# audio.net
KiCad netlist of a schematic drawn in Altium Designer
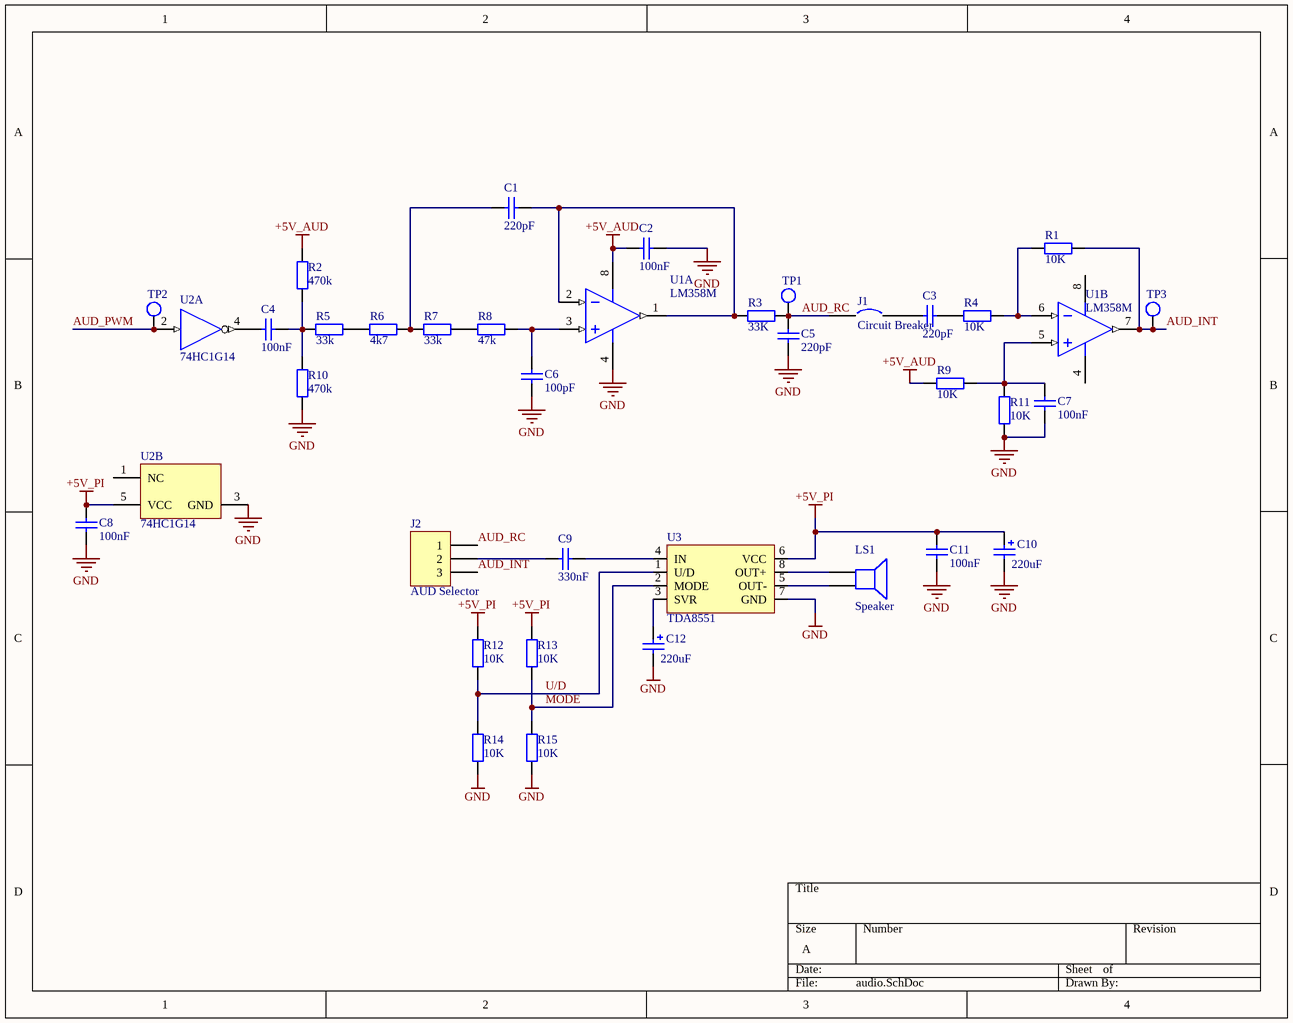
[diagram p0: audio.SchDoc]

(export (version "E")
  (design (tool "Eeschema 10.0.6"))
  (components
    (comp (ref "C1")
      (value "220pF")
      (footprint "6-0805_M")
      (description "Capacitor")
      (fields (field (name "Comment") "Cap") (field (name "PUBLISHER") "Altium Limited"))
      (libsource (lib "Miscellaneous Devices") (part "Cap"))
    )
    (comp (ref "C2")
      (value "100nF")
      (footprint "6-0805_M")
      (description "Capacitor")
      (fields (field (name "Comment") "Cap") (field (name "PUBLISHER") "Altium Limited"))
      (libsource (lib "Miscellaneous Devices") (part "Cap"))
    )
    (comp (ref "C3")
      (value "220pF")
      (footprint "6-0805_M")
      (description "Capacitor")
      (fields (field (name "Comment") "Cap") (field (name "PUBLISHER") "Altium Limited"))
      (libsource (lib "Miscellaneous Devices") (part "Cap"))
    )
    (comp (ref "C4")
      (value "100nF")
      (footprint "6-0805_M")
      (description "Capacitor")
      (fields (field (name "Comment") "Cap") (field (name "PUBLISHER") "Altium Limited"))
      (libsource (lib "Miscellaneous Devices") (part "Cap"))
    )
    (comp (ref "C5")
      (value "220pF")
      (footprint "6-0805_M")
      (description "Capacitor")
      (fields (field (name "Comment") "Cap") (field (name "PUBLISHER") "Altium Limited"))
      (libsource (lib "Miscellaneous Devices") (part "Cap"))
    )
    (comp (ref "C6")
      (value "100pF")
      (footprint "6-0805_M")
      (description "Capacitor")
      (fields (field (name "Comment") "Cap") (field (name "PUBLISHER") "Altium Limited"))
      (libsource (lib "Miscellaneous Devices") (part "Cap"))
    )
    (comp (ref "C7")
      (value "100nF")
      (footprint "6-0805_M")
      (description "Capacitor")
      (fields (field (name "Comment") "Cap") (field (name "PUBLISHER") "Altium Limited"))
      (libsource (lib "Miscellaneous Devices") (part "Cap"))
    )
    (comp (ref "C8")
      (value "100nF")
      (footprint "6-0805_M")
      (description "Capacitor")
      (fields (field (name "Comment") "Cap") (field (name "PUBLISHER") "Altium Limited"))
      (libsource (lib "Miscellaneous Devices") (part "Cap"))
    )
    (comp (ref "C9")
      (value "330nF")
      (footprint "6-0805_M")
      (description "Capacitor")
      (fields (field (name "Comment") "Cap") (field (name "PUBLISHER") "Altium Limited"))
      (libsource (lib "Miscellaneous Devices") (part "Cap"))
    )
    (comp (ref "C10")
      (value "220uF")
      (footprint "EEEFK1H")
      (description "Polarized Capacitor (Axial)")
      (fields (field (name "Comment") "Cap Pol2") (field (name "PUBLISHER") "Altium Limited"))
      (libsource (lib "Miscellaneous Devices") (part "Cap Pol2"))
    )
    (comp (ref "C11")
      (value "100nF")
      (footprint "6-0805_M")
      (description "Capacitor")
      (fields (field (name "Comment") "Cap") (field (name "PUBLISHER") "Altium Limited"))
      (libsource (lib "Miscellaneous Devices") (part "Cap"))
    )
    (comp (ref "C12")
      (value "220uF")
      (footprint "EEEFK1H")
      (description "Polarized Capacitor (Axial)")
      (fields (field (name "Comment") "Cap Pol2") (field (name "PUBLISHER") "Altium Limited"))
      (libsource (lib "Miscellaneous Devices") (part "Cap Pol2"))
    )
    (comp (ref "J1")
      (value "Circuit Breaker")
      (footprint "SOLDER_JUMPER_24mil")
      (fields (field (name "PUBLISHER") "Altium Limited"))
      (libsource (lib "Miscellaneous Devices") (part "Circuit Breaker"))
    )
    (comp (ref "J2")
      (value "AUD Selector")
      (footprint "SOLDER_SELECTOR_24mil")
      (description "Header, 3-Pin")
      (fields (field (name "PUBLISHER") "Altium Limited"))
      (libsource (lib "Miscellaneous Connectors") (part "Header 3"))
    )
    (comp (ref "LS1")
      (value "Speaker")
      (footprint "HDR1X2")
      (description "Loudspeaker")
      (fields (field (name "PUBLISHER") "Altium Limited"))
      (libsource (lib "Miscellaneous Devices") (part "Speaker"))
    )
    (comp (ref "R1")
      (value "10K")
      (footprint "6-0805_M")
      (description "Resistor")
      (fields (field (name "Comment") "Res2") (field (name "PUBLISHER") "Altium Limited"))
      (libsource (lib "Miscellaneous Devices") (part "Res2"))
    )
    (comp (ref "R2")
      (value "470k")
      (footprint "6-0805_M")
      (description "Resistor")
      (fields (field (name "Comment") "Res2") (field (name "PUBLISHER") "Altium Limited"))
      (libsource (lib "") (part "Res2_1"))
    )
    (comp (ref "R3")
      (value "33K")
      (footprint "6-0805_M")
      (description "Resistor")
      (fields (field (name "Comment") "Res2") (field (name "PUBLISHER") "Altium Limited"))
      (libsource (lib "Miscellaneous Devices") (part "Res2"))
    )
    (comp (ref "R4")
      (value "10K")
      (footprint "6-0805_M")
      (description "Resistor")
      (fields (field (name "Comment") "Res2") (field (name "PUBLISHER") "Altium Limited"))
      (libsource (lib "Miscellaneous Devices") (part "Res2"))
    )
    (comp (ref "R5")
      (value "33k")
      (footprint "6-0805_M")
      (description "Resistor")
      (fields (field (name "Comment") "Res2") (field (name "PUBLISHER") "Altium Limited"))
      (libsource (lib "Miscellaneous Devices") (part "Res2"))
    )
    (comp (ref "R6")
      (value "4k7")
      (footprint "6-0805_M")
      (description "Resistor")
      (fields (field (name "Comment") "Res2") (field (name "PUBLISHER") "Altium Limited"))
      (libsource (lib "Miscellaneous Devices") (part "Res2"))
    )
    (comp (ref "R7")
      (value "33k")
      (footprint "6-0805_M")
      (description "Resistor")
      (fields (field (name "Comment") "Res2") (field (name "PUBLISHER") "Altium Limited"))
      (libsource (lib "Miscellaneous Devices") (part "Res2"))
    )
    (comp (ref "R8")
      (value "47k")
      (footprint "6-0805_M")
      (description "Resistor")
      (fields (field (name "Comment") "Res2") (field (name "PUBLISHER") "Altium Limited"))
      (libsource (lib "Miscellaneous Devices") (part "Res2"))
    )
    (comp (ref "R9")
      (value "10K")
      (footprint "6-0805_M")
      (description "Resistor")
      (fields (field (name "Comment") "Res2") (field (name "PUBLISHER") "Altium Limited"))
      (libsource (lib "Miscellaneous Devices") (part "Res2"))
    )
    (comp (ref "R10")
      (value "470k")
      (footprint "6-0805_M")
      (description "Resistor")
      (fields (field (name "Comment") "Res2") (field (name "PUBLISHER") "Altium Limited"))
      (libsource (lib "") (part "Res2_1"))
    )
    (comp (ref "R11")
      (value "10K")
      (footprint "6-0805_M")
      (description "Resistor")
      (fields (field (name "Comment") "Res2") (field (name "PUBLISHER") "Altium Limited"))
      (libsource (lib "") (part "Res2_1"))
    )
    (comp (ref "R12")
      (value "10K")
      (footprint "6-0805_M")
      (description "Resistor")
      (fields (field (name "Comment") "Res2") (field (name "PUBLISHER") "Altium Limited"))
      (libsource (lib "") (part "Res2_1"))
    )
    (comp (ref "R13")
      (value "10K")
      (footprint "6-0805_M")
      (description "Resistor")
      (fields (field (name "Comment") "Res2") (field (name "PUBLISHER") "Altium Limited"))
      (libsource (lib "") (part "Res2_1"))
    )
    (comp (ref "R14")
      (value "10K")
      (footprint "6-0805_M")
      (description "Resistor")
      (fields (field (name "Comment") "Res2") (field (name "PUBLISHER") "Altium Limited"))
      (libsource (lib "") (part "Res2_1"))
    )
    (comp (ref "R15")
      (value "10K")
      (footprint "6-0805_M")
      (description "Resistor")
      (fields (field (name "Comment") "Res2") (field (name "PUBLISHER") "Altium Limited"))
      (libsource (lib "") (part "Res2_1"))
    )
    (comp (ref "TP1")
      (value "TestPoint")
      (footprint "MEASUREMENT_POINT")
      (description "Testpoint")
      (libsource (lib "clusterlib") (part "TestPoint"))
    )
    (comp (ref "TP2")
      (value "TestPoint")
      (footprint "MEASUREMENT_POINT")
      (description "Testpoint")
      (libsource (lib "clusterlib") (part "TestPoint"))
    )
    (comp (ref "TP3")
      (value "TestPoint")
      (footprint "MEASUREMENT_POINT")
      (description "Testpoint")
      (libsource (lib "clusterlib") (part "TestPoint"))
    )
    (comp (ref "U1")
      (value "LM358M")
      (footprint "M08A_N")
      (description "Low Power Dual Operational Amplifier, 8-pin Narrow SOIC")
      (fields (field (name "MANUFACTURER") "National Semiconductor"))
      (libsource (lib "National Semiconductor Amplifier") (part "LM358M"))
    )
    (comp (ref "U2")
      (value "74HC1G14")
      (footprint "DBV0005A_N")
      (description "Single Schmitt-Trigger Inverter Gate, DBV0005A, SMALL T&R")
      (fields
        (field (name "GENERIC PART NUMBER") "SN74AHC1G14")
        (field (name "MANUFACTURER") "Texas Instruments")
      )
      (libsource (lib "TI_Logic_Little_Logic") (part "SN74AHC1G14DBVT"))
    )
    (comp (ref "U3")
      (value "TDA8551")
      (footprint "SOIC-8")
      (description "TDA8551 1W Audio Amplifier")
      (libsource (lib "clusterlib") (part "TDA8551"))
    )
  )
  (nets
    (net (code "1") (name "+5V_AUD") (class "Default")
      (node (ref "C2") (pin "2") (pinfunction "2_2") (pintype "passive"))
      (node (ref "R2") (pin "2") (pinfunction "2_2") (pintype "passive"))
      (node (ref "R9") (pin "1") (pinfunction "1_1") (pintype "passive"))
      (node (ref "U1") (pin "8") (pinfunction "V+_8") (pintype "power_in"))
    )
    (net (code "2") (name "+5V_PI") (class "Default")
      (node (ref "C10") (pin "1") (pinfunction "1_1") (pintype "passive"))
      (node (ref "C11") (pin "1") (pinfunction "1_1") (pintype "passive"))
      (node (ref "C8") (pin "1") (pinfunction "1_1") (pintype "passive"))
      (node (ref "R12") (pin "2") (pinfunction "2_2") (pintype "passive"))
      (node (ref "R13") (pin "2") (pinfunction "2_2") (pintype "passive"))
      (node (ref "U2") (pin "5") (pinfunction "VCC_5") (pintype "power_in"))
      (node (ref "U3") (pin "6") (pinfunction "VCC_6") (pintype "passive"))
    )
    (net (code "3") (name "/AUD_INT") (class "Default")
      (node (ref "J2") (pin "3") (pinfunction "3_3") (pintype "passive"))
      (node (ref "R1") (pin "2") (pinfunction "2_2") (pintype "passive"))
      (node (ref "TP3") (pin "1") (pinfunction "1_1") (pintype "passive"))
      (node (ref "U1") (pin "7") (pinfunction "OUTB_7") (pintype "output"))
    )
    (net (code "4") (name "/AUD_PWM") (class "Default")
      (node (ref "TP2") (pin "1") (pinfunction "1_1") (pintype "passive"))
      (node (ref "U2") (pin "2") (pinfunction "A_2") (pintype "input"))
    )
    (net (code "5") (name "/AUD_RC") (class "Default")
      (node (ref "C5") (pin "2") (pinfunction "2_2") (pintype "passive"))
      (node (ref "J1") (pin "1") (pinfunction "1_1") (pintype "passive"))
      (node (ref "J2") (pin "1") (pinfunction "1_1") (pintype "passive"))
      (node (ref "R3") (pin "2") (pinfunction "2_2") (pintype "passive"))
      (node (ref "TP1") (pin "1") (pinfunction "1_1") (pintype "passive"))
    )
    (net (code "6") (name "/MODE") (class "Default")
      (node (ref "R13") (pin "1") (pinfunction "1_1") (pintype "passive"))
      (node (ref "R15") (pin "2") (pinfunction "2_2") (pintype "passive"))
      (node (ref "U3") (pin "2") (pinfunction "MODE_2") (pintype "passive"))
    )
    (net (code "7") (name "/U{slash}D") (class "Default")
      (node (ref "R12") (pin "1") (pinfunction "1_1") (pintype "passive"))
      (node (ref "R14") (pin "2") (pinfunction "2_2") (pintype "passive"))
      (node (ref "U3") (pin "1") (pinfunction "U/D_1") (pintype "passive"))
    )
    (net (code "8") (name "GND") (class "Default")
      (node (ref "C10") (pin "2") (pinfunction "2_2") (pintype "passive"))
      (node (ref "C11") (pin "2") (pinfunction "2_2") (pintype "passive"))
      (node (ref "C12") (pin "2") (pinfunction "2_2") (pintype "passive"))
      (node (ref "C2") (pin "1") (pinfunction "1_1") (pintype "passive"))
      (node (ref "C5") (pin "1") (pinfunction "1_1") (pintype "passive"))
      (node (ref "C6") (pin "2") (pinfunction "2_2") (pintype "passive"))
      (node (ref "C7") (pin "2") (pinfunction "2_2") (pintype "passive"))
      (node (ref "C8") (pin "2") (pinfunction "2_2") (pintype "passive"))
      (node (ref "R10") (pin "1") (pinfunction "1_1") (pintype "passive"))
      (node (ref "R11") (pin "1") (pinfunction "1_1") (pintype "passive"))
      (node (ref "R14") (pin "1") (pinfunction "1_1") (pintype "passive"))
      (node (ref "R15") (pin "1") (pinfunction "1_1") (pintype "passive"))
      (node (ref "U1") (pin "4") (pinfunction "GND_4") (pintype "power_in"))
      (node (ref "U2") (pin "3") (pinfunction "GND_3") (pintype "power_in"))
      (node (ref "U3") (pin "7") (pinfunction "GND_7") (pintype "passive"))
    )
    (net (code "9") (name "Net-(C1-Pad2)") (class "Default")
      (node (ref "C1") (pin "2") (pinfunction "2_2") (pintype "passive"))
      (node (ref "R6") (pin "2") (pinfunction "2_2") (pintype "passive"))
      (node (ref "R7") (pin "1") (pinfunction "1_1") (pintype "passive"))
    )
    (net (code "10") (name "Net-(C3-Pad1)") (class "Default")
      (node (ref "C3") (pin "1") (pinfunction "1_1") (pintype "passive"))
      (node (ref "R4") (pin "1") (pinfunction "1_1") (pintype "passive"))
    )
    (net (code "11") (name "Net-(C3-Pad2)") (class "Default")
      (node (ref "C3") (pin "2") (pinfunction "2_2") (pintype "passive"))
      (node (ref "J1") (pin "2") (pinfunction "2_2") (pintype "passive"))
    )
    (net (code "12") (name "Net-(C4-Pad1)") (class "Default")
      (node (ref "C4") (pin "1") (pinfunction "1_1") (pintype "passive"))
      (node (ref "R10") (pin "2") (pinfunction "2_2") (pintype "passive"))
      (node (ref "R2") (pin "1") (pinfunction "1_1") (pintype "passive"))
      (node (ref "R5") (pin "1") (pinfunction "1_1") (pintype "passive"))
    )
    (net (code "13") (name "Net-(C9-Pad2)") (class "Default")
      (node (ref "C9") (pin "2") (pinfunction "2_2") (pintype "passive"))
      (node (ref "J2") (pin "2") (pinfunction "2_2") (pintype "passive"))
    )
    (net (code "14") (name "Net-(R5-Pad2)") (class "Default")
      (node (ref "R5") (pin "2") (pinfunction "2_2") (pintype "passive"))
      (node (ref "R6") (pin "1") (pinfunction "1_1") (pintype "passive"))
    )
    (net (code "15") (name "Net-(R7-Pad2)") (class "Default")
      (node (ref "R7") (pin "2") (pinfunction "2_2") (pintype "passive"))
      (node (ref "R8") (pin "1") (pinfunction "1_1") (pintype "passive"))
    )
    (net (code "16") (name "Net-(U1A-INA+)") (class "Default")
      (node (ref "C6") (pin "1") (pinfunction "1_1") (pintype "passive"))
      (node (ref "R8") (pin "2") (pinfunction "2_2") (pintype "passive"))
      (node (ref "U1") (pin "3") (pinfunction "INA+_3") (pintype "input"))
    )
    (net (code "17") (name "Net-(U1A-INA-)") (class "Default")
      (node (ref "C1") (pin "1") (pinfunction "1_1") (pintype "passive"))
      (node (ref "R3") (pin "1") (pinfunction "1_1") (pintype "passive"))
      (node (ref "U1") (pin "1") (pinfunction "OUTA_1") (pintype "output"))
      (node (ref "U1") (pin "2") (pinfunction "INA-_2") (pintype "input"))
    )
    (net (code "18") (name "Net-(U1B-INB+)") (class "Default")
      (node (ref "C7") (pin "1") (pinfunction "1_1") (pintype "passive"))
      (node (ref "R11") (pin "2") (pinfunction "2_2") (pintype "passive"))
      (node (ref "R9") (pin "2") (pinfunction "2_2") (pintype "passive"))
      (node (ref "U1") (pin "5") (pinfunction "INB+_5") (pintype "input"))
    )
    (net (code "19") (name "Net-(U1B-INB-)") (class "Default")
      (node (ref "R1") (pin "1") (pinfunction "1_1") (pintype "passive"))
      (node (ref "R4") (pin "2") (pinfunction "2_2") (pintype "passive"))
      (node (ref "U1") (pin "6") (pinfunction "INB-_6") (pintype "input"))
    )
    (net (code "20") (name "Net-(U2A-Y)") (class "Default")
      (node (ref "C4") (pin "2") (pinfunction "2_2") (pintype "passive"))
      (node (ref "U2") (pin "4") (pinfunction "Y_4") (pintype "output"))
    )
    (net (code "21") (name "Net-(U3-IN)") (class "Default")
      (node (ref "C9") (pin "1") (pinfunction "1_1") (pintype "passive"))
      (node (ref "U3") (pin "4") (pinfunction "IN_4") (pintype "passive"))
    )
    (net (code "22") (name "Net-(U3-OUT+)") (class "Default")
      (node (ref "LS1") (pin "1") (pinfunction "1_1") (pintype "passive"))
      (node (ref "U3") (pin "8") (pinfunction "OUT+_8") (pintype "passive"))
    )
    (net (code "23") (name "Net-(U3-OUT-)") (class "Default")
      (node (ref "LS1") (pin "2") (pinfunction "2_2") (pintype "passive"))
      (node (ref "U3") (pin "5") (pinfunction "OUT-_5") (pintype "passive"))
    )
    (net (code "24") (name "Net-(U3-SVR)") (class "Default")
      (node (ref "C12") (pin "1") (pinfunction "1_1") (pintype "passive"))
      (node (ref "U3") (pin "3") (pinfunction "SVR_3") (pintype "passive"))
    )
    (net (code "25") (name "unconnected-(U1B-GND-Pad4)") (class "Default")
      (node (ref "U1") (pin "4") (pinfunction "GND_4") (pintype "power_in"))
    )
    (net (code "26") (name "unconnected-(U1B-V+-Pad8)") (class "Default")
      (node (ref "U1") (pin "8") (pinfunction "V+_8") (pintype "power_in"))
    )
    (net (code "27") (name "unconnected-(U2B-NC-Pad1)") (class "Default")
      (node (ref "U2") (pin "1") (pinfunction "NC_1") (pintype "passive"))
    )
  )
)
